# mux1.net
KiCad netlist of a schematic drawn in EAGLE
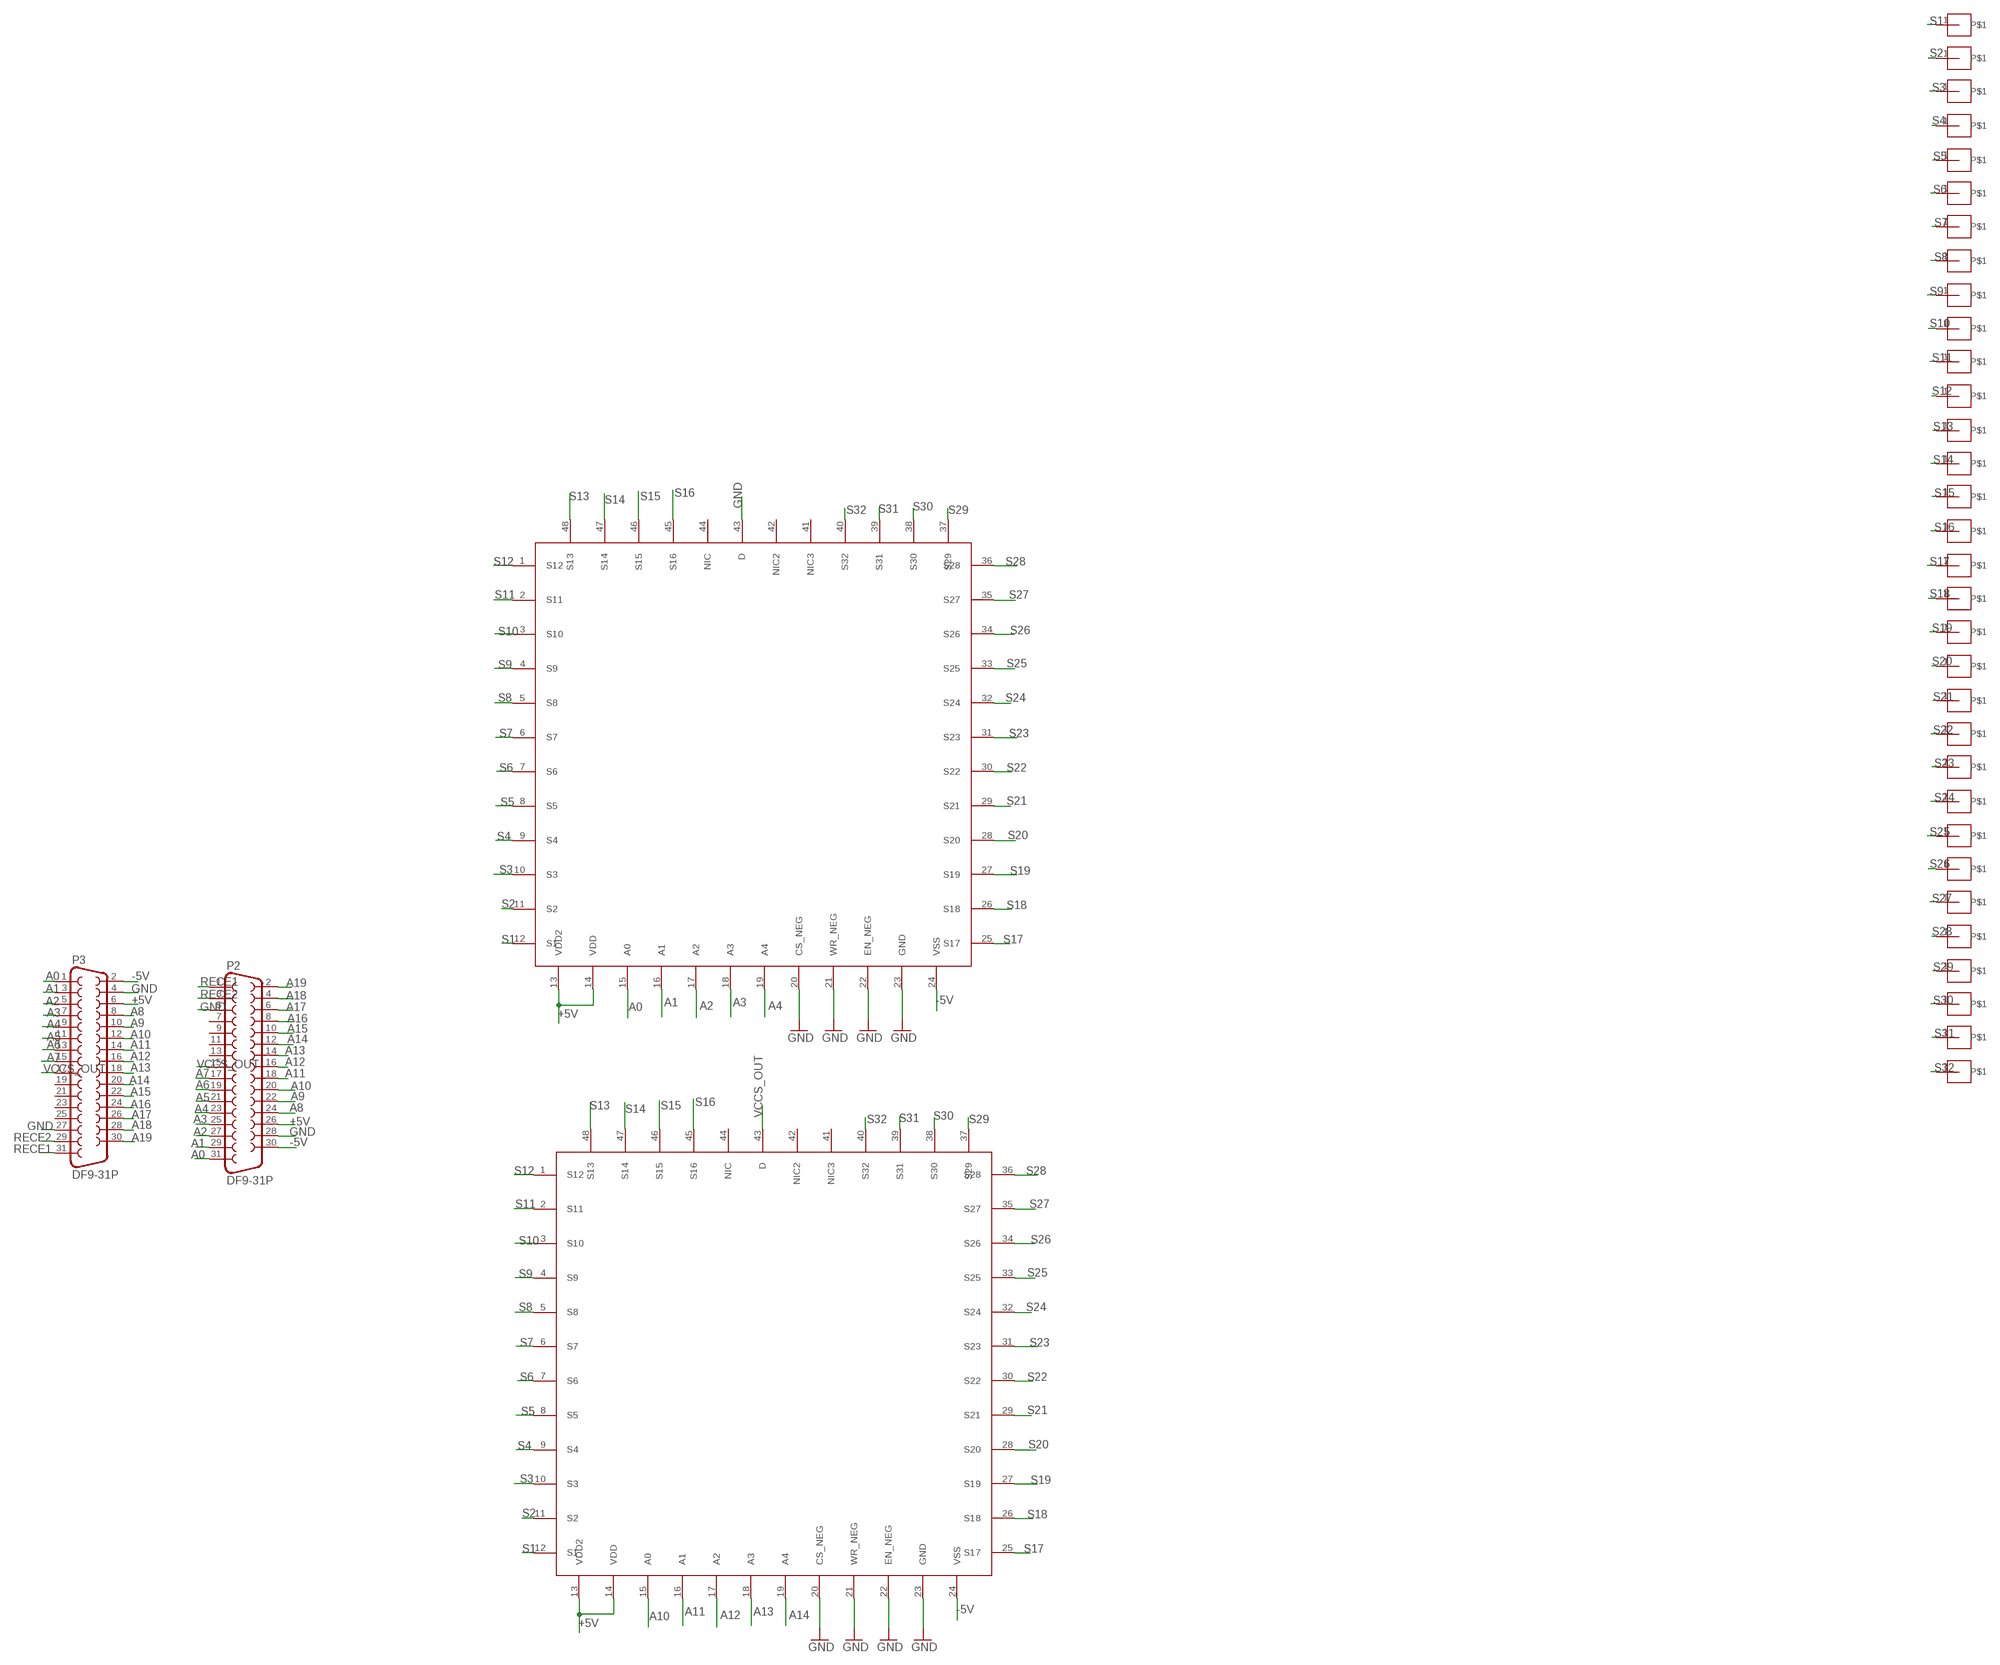
[diagram p0: schematic, sheet 1]

(export (version "E")
  (design (tool "Eeschema 10.0.6"))
  (components
    (comp (ref "P2")
      (value "DF9-31P")
      (footprint "eagle-import:DF9-31P")
      (libsource (lib "eagle-import") (part "DF9-31P"))
    )
    (comp (ref "P3")
      (value "DF9-31P")
      (footprint "eagle-import:DF9-31P")
      (libsource (lib "eagle-import") (part "DF9-31P"))
    )
    (comp (ref "U$3")
      (value "ADG732")
      (footprint "eagle-import:TQFP48")
      (libsource (lib "eagle-import") (part "ADG732"))
    )
    (comp (ref "U$21")
      (value "ADG732")
      (footprint "eagle-import:TQFP48")
      (libsource (lib "eagle-import") (part "ADG732"))
    )
    (comp (ref "U$25")
      (value "M01")
      (footprint "eagle-import:M01")
      (libsource (lib "eagle-import") (part "M01"))
    )
    (comp (ref "U$26")
      (value "M01")
      (footprint "eagle-import:M01")
      (libsource (lib "eagle-import") (part "M01"))
    )
    (comp (ref "U$27")
      (value "M01")
      (footprint "eagle-import:M01")
      (libsource (lib "eagle-import") (part "M01"))
    )
    (comp (ref "U$28")
      (value "M01")
      (footprint "eagle-import:M01")
      (libsource (lib "eagle-import") (part "M01"))
    )
    (comp (ref "U$29")
      (value "M01")
      (footprint "eagle-import:M01")
      (libsource (lib "eagle-import") (part "M01"))
    )
    (comp (ref "U$30")
      (value "M01")
      (footprint "eagle-import:M01")
      (libsource (lib "eagle-import") (part "M01"))
    )
    (comp (ref "U$31")
      (value "M01")
      (footprint "eagle-import:M01")
      (libsource (lib "eagle-import") (part "M01"))
    )
    (comp (ref "U$32")
      (value "M01")
      (footprint "eagle-import:M01")
      (libsource (lib "eagle-import") (part "M01"))
    )
    (comp (ref "U$33")
      (value "M01")
      (footprint "eagle-import:M01")
      (libsource (lib "eagle-import") (part "M01"))
    )
    (comp (ref "U$34")
      (value "M01")
      (footprint "eagle-import:M01")
      (libsource (lib "eagle-import") (part "M01"))
    )
    (comp (ref "U$35")
      (value "M01")
      (footprint "eagle-import:M01")
      (libsource (lib "eagle-import") (part "M01"))
    )
    (comp (ref "U$36")
      (value "M01")
      (footprint "eagle-import:M01")
      (libsource (lib "eagle-import") (part "M01"))
    )
    (comp (ref "U$37")
      (value "M01")
      (footprint "eagle-import:M01")
      (libsource (lib "eagle-import") (part "M01"))
    )
    (comp (ref "U$38")
      (value "M01")
      (footprint "eagle-import:M01")
      (libsource (lib "eagle-import") (part "M01"))
    )
    (comp (ref "U$39")
      (value "M01")
      (footprint "eagle-import:M01")
      (libsource (lib "eagle-import") (part "M01"))
    )
    (comp (ref "U$40")
      (value "M01")
      (footprint "eagle-import:M01")
      (libsource (lib "eagle-import") (part "M01"))
    )
    (comp (ref "U$41")
      (value "M01")
      (footprint "eagle-import:M01")
      (libsource (lib "eagle-import") (part "M01"))
    )
    (comp (ref "U$42")
      (value "M01")
      (footprint "eagle-import:M01")
      (libsource (lib "eagle-import") (part "M01"))
    )
    (comp (ref "U$43")
      (value "M01")
      (footprint "eagle-import:M01")
      (libsource (lib "eagle-import") (part "M01"))
    )
    (comp (ref "U$44")
      (value "M01")
      (footprint "eagle-import:M01")
      (libsource (lib "eagle-import") (part "M01"))
    )
    (comp (ref "U$45")
      (value "M01")
      (footprint "eagle-import:M01")
      (libsource (lib "eagle-import") (part "M01"))
    )
    (comp (ref "U$46")
      (value "M01")
      (footprint "eagle-import:M01")
      (libsource (lib "eagle-import") (part "M01"))
    )
    (comp (ref "U$47")
      (value "M01")
      (footprint "eagle-import:M01")
      (libsource (lib "eagle-import") (part "M01"))
    )
    (comp (ref "U$48")
      (value "M01")
      (footprint "eagle-import:M01")
      (libsource (lib "eagle-import") (part "M01"))
    )
    (comp (ref "U$49")
      (value "M01")
      (footprint "eagle-import:M01")
      (libsource (lib "eagle-import") (part "M01"))
    )
    (comp (ref "U$50")
      (value "M01")
      (footprint "eagle-import:M01")
      (libsource (lib "eagle-import") (part "M01"))
    )
    (comp (ref "U$51")
      (value "M01")
      (footprint "eagle-import:M01")
      (libsource (lib "eagle-import") (part "M01"))
    )
    (comp (ref "U$52")
      (value "M01")
      (footprint "eagle-import:M01")
      (libsource (lib "eagle-import") (part "M01"))
    )
    (comp (ref "U$53")
      (value "M01")
      (footprint "eagle-import:M01")
      (libsource (lib "eagle-import") (part "M01"))
    )
    (comp (ref "U$54")
      (value "M01")
      (footprint "eagle-import:M01")
      (libsource (lib "eagle-import") (part "M01"))
    )
    (comp (ref "U$55")
      (value "M01")
      (footprint "eagle-import:M01")
      (libsource (lib "eagle-import") (part "M01"))
    )
    (comp (ref "U$56")
      (value "M01")
      (footprint "eagle-import:M01")
      (libsource (lib "eagle-import") (part "M01"))
    )
  )
  (nets
    (net (code "1") (name "/+5V") (class "Default")
      (node (ref "P2") (pin "26") (pinfunction "26_26") (pintype "passive"))
      (node (ref "P3") (pin "6") (pinfunction "6_6") (pintype "passive"))
      (node (ref "U$21") (pin "13") (pinfunction "VDD2_13") (pintype "bidirectional"))
      (node (ref "U$21") (pin "14") (pinfunction "VDD_14") (pintype "bidirectional"))
      (node (ref "U$3") (pin "13") (pinfunction "VDD2_13") (pintype "bidirectional"))
      (node (ref "U$3") (pin "14") (pinfunction "VDD_14") (pintype "bidirectional"))
    )
    (net (code "2") (name "/-5V") (class "Default")
      (node (ref "P2") (pin "30") (pinfunction "30_30") (pintype "passive"))
      (node (ref "P3") (pin "2") (pinfunction "2_2") (pintype "passive"))
      (node (ref "U$21") (pin "24") (pinfunction "VSS_24") (pintype "bidirectional"))
      (node (ref "U$3") (pin "24") (pinfunction "VSS_24") (pintype "bidirectional"))
    )
    (net (code "3") (name "/A0") (class "Default")
      (node (ref "P2") (pin "31") (pinfunction "31_31") (pintype "passive"))
      (node (ref "P3") (pin "1") (pinfunction "1_1") (pintype "passive"))
      (node (ref "U$3") (pin "15") (pinfunction "A0_15") (pintype "bidirectional"))
    )
    (net (code "4") (name "/A1") (class "Default")
      (node (ref "P2") (pin "29") (pinfunction "29_29") (pintype "passive"))
      (node (ref "P3") (pin "3") (pinfunction "3_3") (pintype "passive"))
      (node (ref "U$3") (pin "16") (pinfunction "A1_16") (pintype "bidirectional"))
    )
    (net (code "5") (name "/A2") (class "Default")
      (node (ref "P2") (pin "27") (pinfunction "27_27") (pintype "passive"))
      (node (ref "P3") (pin "5") (pinfunction "5_5") (pintype "passive"))
      (node (ref "U$3") (pin "17") (pinfunction "A2_17") (pintype "bidirectional"))
    )
    (net (code "6") (name "/A3") (class "Default")
      (node (ref "P2") (pin "25") (pinfunction "25_25") (pintype "passive"))
      (node (ref "P3") (pin "7") (pinfunction "7_7") (pintype "passive"))
      (node (ref "U$3") (pin "18") (pinfunction "A3_18") (pintype "bidirectional"))
    )
    (net (code "7") (name "/A4") (class "Default")
      (node (ref "P2") (pin "23") (pinfunction "23_23") (pintype "passive"))
      (node (ref "P3") (pin "9") (pinfunction "9_9") (pintype "passive"))
      (node (ref "U$3") (pin "19") (pinfunction "A4_19") (pintype "bidirectional"))
    )
    (net (code "8") (name "/A5") (class "Default")
      (node (ref "P2") (pin "21") (pinfunction "21_21") (pintype "passive"))
      (node (ref "P3") (pin "11") (pinfunction "11_11") (pintype "passive"))
    )
    (net (code "9") (name "/A6") (class "Default")
      (node (ref "P2") (pin "19") (pinfunction "19_19") (pintype "passive"))
      (node (ref "P3") (pin "13") (pinfunction "13_13") (pintype "passive"))
    )
    (net (code "10") (name "/A7") (class "Default")
      (node (ref "P2") (pin "17") (pinfunction "17_17") (pintype "passive"))
      (node (ref "P3") (pin "15") (pinfunction "15_15") (pintype "passive"))
    )
    (net (code "11") (name "/A8") (class "Default")
      (node (ref "P2") (pin "24") (pinfunction "24_24") (pintype "passive"))
      (node (ref "P3") (pin "8") (pinfunction "8_8") (pintype "passive"))
    )
    (net (code "12") (name "/A9") (class "Default")
      (node (ref "P2") (pin "22") (pinfunction "22_22") (pintype "passive"))
      (node (ref "P3") (pin "10") (pinfunction "10_10") (pintype "passive"))
    )
    (net (code "13") (name "/A10") (class "Default")
      (node (ref "P2") (pin "20") (pinfunction "20_20") (pintype "passive"))
      (node (ref "P3") (pin "12") (pinfunction "12_12") (pintype "passive"))
      (node (ref "U$21") (pin "15") (pinfunction "A0_15") (pintype "bidirectional"))
    )
    (net (code "14") (name "/A11") (class "Default")
      (node (ref "P2") (pin "18") (pinfunction "18_18") (pintype "passive"))
      (node (ref "P3") (pin "14") (pinfunction "14_14") (pintype "passive"))
      (node (ref "U$21") (pin "16") (pinfunction "A1_16") (pintype "bidirectional"))
    )
    (net (code "15") (name "/A12") (class "Default")
      (node (ref "P2") (pin "16") (pinfunction "16_16") (pintype "passive"))
      (node (ref "P3") (pin "16") (pinfunction "16_16") (pintype "passive"))
      (node (ref "U$21") (pin "17") (pinfunction "A2_17") (pintype "bidirectional"))
    )
    (net (code "16") (name "/A13") (class "Default")
      (node (ref "P2") (pin "14") (pinfunction "14_14") (pintype "passive"))
      (node (ref "P3") (pin "18") (pinfunction "18_18") (pintype "passive"))
      (node (ref "U$21") (pin "18") (pinfunction "A3_18") (pintype "bidirectional"))
    )
    (net (code "17") (name "/A14") (class "Default")
      (node (ref "P2") (pin "12") (pinfunction "12_12") (pintype "passive"))
      (node (ref "P3") (pin "20") (pinfunction "20_20") (pintype "passive"))
      (node (ref "U$21") (pin "19") (pinfunction "A4_19") (pintype "bidirectional"))
    )
    (net (code "18") (name "/A15") (class "Default")
      (node (ref "P2") (pin "10") (pinfunction "10_10") (pintype "passive"))
      (node (ref "P3") (pin "22") (pinfunction "22_22") (pintype "passive"))
    )
    (net (code "19") (name "/A16") (class "Default")
      (node (ref "P2") (pin "8") (pinfunction "8_8") (pintype "passive"))
      (node (ref "P3") (pin "24") (pinfunction "24_24") (pintype "passive"))
    )
    (net (code "20") (name "/A17") (class "Default")
      (node (ref "P2") (pin "6") (pinfunction "6_6") (pintype "passive"))
      (node (ref "P3") (pin "26") (pinfunction "26_26") (pintype "passive"))
    )
    (net (code "21") (name "/A18") (class "Default")
      (node (ref "P2") (pin "4") (pinfunction "4_4") (pintype "passive"))
      (node (ref "P3") (pin "28") (pinfunction "28_28") (pintype "passive"))
    )
    (net (code "22") (name "/A19") (class "Default")
      (node (ref "P2") (pin "2") (pinfunction "2_2") (pintype "passive"))
      (node (ref "P3") (pin "30") (pinfunction "30_30") (pintype "passive"))
    )
    (net (code "23") (name "/RECE1") (class "Default")
      (node (ref "P2") (pin "1") (pinfunction "1_1") (pintype "passive"))
      (node (ref "P3") (pin "31") (pinfunction "31_31") (pintype "passive"))
    )
    (net (code "24") (name "/RECE2") (class "Default")
      (node (ref "P2") (pin "3") (pinfunction "3_3") (pintype "passive"))
      (node (ref "P3") (pin "29") (pinfunction "29_29") (pintype "passive"))
    )
    (net (code "25") (name "/S1") (class "Default")
      (node (ref "U$21") (pin "12") (pinfunction "S1_12") (pintype "bidirectional"))
      (node (ref "U$25") (pin "1") (pinfunction "P$1_1") (pintype "bidirectional"))
      (node (ref "U$3") (pin "12") (pinfunction "S1_12") (pintype "bidirectional"))
    )
    (net (code "26") (name "/S2") (class "Default")
      (node (ref "U$21") (pin "11") (pinfunction "S2_11") (pintype "bidirectional"))
      (node (ref "U$26") (pin "1") (pinfunction "P$1_1") (pintype "bidirectional"))
      (node (ref "U$3") (pin "11") (pinfunction "S2_11") (pintype "bidirectional"))
    )
    (net (code "27") (name "/S3") (class "Default")
      (node (ref "U$21") (pin "10") (pinfunction "S3_10") (pintype "bidirectional"))
      (node (ref "U$27") (pin "1") (pinfunction "P$1_1") (pintype "bidirectional"))
      (node (ref "U$3") (pin "10") (pinfunction "S3_10") (pintype "bidirectional"))
    )
    (net (code "28") (name "/S4") (class "Default")
      (node (ref "U$21") (pin "9") (pinfunction "S4_9") (pintype "bidirectional"))
      (node (ref "U$28") (pin "1") (pinfunction "P$1_1") (pintype "bidirectional"))
      (node (ref "U$3") (pin "9") (pinfunction "S4_9") (pintype "bidirectional"))
    )
    (net (code "29") (name "/S5") (class "Default")
      (node (ref "U$21") (pin "8") (pinfunction "S5_8") (pintype "bidirectional"))
      (node (ref "U$29") (pin "1") (pinfunction "P$1_1") (pintype "bidirectional"))
      (node (ref "U$3") (pin "8") (pinfunction "S5_8") (pintype "bidirectional"))
    )
    (net (code "30") (name "/S6") (class "Default")
      (node (ref "U$21") (pin "7") (pinfunction "S6_7") (pintype "bidirectional"))
      (node (ref "U$3") (pin "7") (pinfunction "S6_7") (pintype "bidirectional"))
      (node (ref "U$30") (pin "1") (pinfunction "P$1_1") (pintype "bidirectional"))
    )
    (net (code "31") (name "/S7") (class "Default")
      (node (ref "U$21") (pin "6") (pinfunction "S7_6") (pintype "bidirectional"))
      (node (ref "U$3") (pin "6") (pinfunction "S7_6") (pintype "bidirectional"))
      (node (ref "U$31") (pin "1") (pinfunction "P$1_1") (pintype "bidirectional"))
    )
    (net (code "32") (name "/S8") (class "Default")
      (node (ref "U$21") (pin "5") (pinfunction "S8_5") (pintype "bidirectional"))
      (node (ref "U$3") (pin "5") (pinfunction "S8_5") (pintype "bidirectional"))
      (node (ref "U$32") (pin "1") (pinfunction "P$1_1") (pintype "bidirectional"))
    )
    (net (code "33") (name "/S9") (class "Default")
      (node (ref "U$21") (pin "4") (pinfunction "S9_4") (pintype "bidirectional"))
      (node (ref "U$3") (pin "4") (pinfunction "S9_4") (pintype "bidirectional"))
      (node (ref "U$33") (pin "1") (pinfunction "P$1_1") (pintype "bidirectional"))
    )
    (net (code "34") (name "/S10") (class "Default")
      (node (ref "U$21") (pin "3") (pinfunction "S10_3") (pintype "bidirectional"))
      (node (ref "U$3") (pin "3") (pinfunction "S10_3") (pintype "bidirectional"))
      (node (ref "U$34") (pin "1") (pinfunction "P$1_1") (pintype "bidirectional"))
    )
    (net (code "35") (name "/S11") (class "Default")
      (node (ref "U$21") (pin "2") (pinfunction "S11_2") (pintype "bidirectional"))
      (node (ref "U$3") (pin "2") (pinfunction "S11_2") (pintype "bidirectional"))
      (node (ref "U$35") (pin "1") (pinfunction "P$1_1") (pintype "bidirectional"))
    )
    (net (code "36") (name "/S12") (class "Default")
      (node (ref "U$21") (pin "1") (pinfunction "S12_1") (pintype "bidirectional"))
      (node (ref "U$3") (pin "1") (pinfunction "S12_1") (pintype "bidirectional"))
      (node (ref "U$36") (pin "1") (pinfunction "P$1_1") (pintype "bidirectional"))
    )
    (net (code "37") (name "/S13") (class "Default")
      (node (ref "U$21") (pin "48") (pinfunction "S13_48") (pintype "bidirectional"))
      (node (ref "U$3") (pin "48") (pinfunction "S13_48") (pintype "bidirectional"))
      (node (ref "U$37") (pin "1") (pinfunction "P$1_1") (pintype "bidirectional"))
    )
    (net (code "38") (name "/S14") (class "Default")
      (node (ref "U$21") (pin "47") (pinfunction "S14_47") (pintype "bidirectional"))
      (node (ref "U$3") (pin "47") (pinfunction "S14_47") (pintype "bidirectional"))
      (node (ref "U$38") (pin "1") (pinfunction "P$1_1") (pintype "bidirectional"))
    )
    (net (code "39") (name "/S15") (class "Default")
      (node (ref "U$21") (pin "46") (pinfunction "S15_46") (pintype "bidirectional"))
      (node (ref "U$3") (pin "46") (pinfunction "S15_46") (pintype "bidirectional"))
      (node (ref "U$39") (pin "1") (pinfunction "P$1_1") (pintype "bidirectional"))
    )
    (net (code "40") (name "/S16") (class "Default")
      (node (ref "U$21") (pin "45") (pinfunction "S16_45") (pintype "bidirectional"))
      (node (ref "U$3") (pin "45") (pinfunction "S16_45") (pintype "bidirectional"))
      (node (ref "U$40") (pin "1") (pinfunction "P$1_1") (pintype "bidirectional"))
    )
    (net (code "41") (name "/S17") (class "Default")
      (node (ref "U$21") (pin "25") (pinfunction "S17_25") (pintype "bidirectional"))
      (node (ref "U$3") (pin "25") (pinfunction "S17_25") (pintype "bidirectional"))
      (node (ref "U$41") (pin "1") (pinfunction "P$1_1") (pintype "bidirectional"))
    )
    (net (code "42") (name "/S18") (class "Default")
      (node (ref "U$21") (pin "26") (pinfunction "S18_26") (pintype "bidirectional"))
      (node (ref "U$3") (pin "26") (pinfunction "S18_26") (pintype "bidirectional"))
      (node (ref "U$42") (pin "1") (pinfunction "P$1_1") (pintype "bidirectional"))
    )
    (net (code "43") (name "/S19") (class "Default")
      (node (ref "U$21") (pin "27") (pinfunction "S19_27") (pintype "bidirectional"))
      (node (ref "U$3") (pin "27") (pinfunction "S19_27") (pintype "bidirectional"))
      (node (ref "U$43") (pin "1") (pinfunction "P$1_1") (pintype "bidirectional"))
    )
    (net (code "44") (name "/S20") (class "Default")
      (node (ref "U$21") (pin "28") (pinfunction "S20_28") (pintype "bidirectional"))
      (node (ref "U$3") (pin "28") (pinfunction "S20_28") (pintype "bidirectional"))
      (node (ref "U$44") (pin "1") (pinfunction "P$1_1") (pintype "bidirectional"))
    )
    (net (code "45") (name "/S21") (class "Default")
      (node (ref "U$21") (pin "29") (pinfunction "S21_29") (pintype "bidirectional"))
      (node (ref "U$3") (pin "29") (pinfunction "S21_29") (pintype "bidirectional"))
      (node (ref "U$45") (pin "1") (pinfunction "P$1_1") (pintype "bidirectional"))
    )
    (net (code "46") (name "/S22") (class "Default")
      (node (ref "U$21") (pin "30") (pinfunction "S22_30") (pintype "bidirectional"))
      (node (ref "U$3") (pin "30") (pinfunction "S22_30") (pintype "bidirectional"))
      (node (ref "U$46") (pin "1") (pinfunction "P$1_1") (pintype "bidirectional"))
    )
    (net (code "47") (name "/S23") (class "Default")
      (node (ref "U$21") (pin "31") (pinfunction "S23_31") (pintype "bidirectional"))
      (node (ref "U$3") (pin "31") (pinfunction "S23_31") (pintype "bidirectional"))
      (node (ref "U$47") (pin "1") (pinfunction "P$1_1") (pintype "bidirectional"))
    )
    (net (code "48") (name "/S24") (class "Default")
      (node (ref "U$21") (pin "32") (pinfunction "S24_32") (pintype "bidirectional"))
      (node (ref "U$3") (pin "32") (pinfunction "S24_32") (pintype "bidirectional"))
      (node (ref "U$48") (pin "1") (pinfunction "P$1_1") (pintype "bidirectional"))
    )
    (net (code "49") (name "/S25") (class "Default")
      (node (ref "U$21") (pin "33") (pinfunction "S25_33") (pintype "bidirectional"))
      (node (ref "U$3") (pin "33") (pinfunction "S25_33") (pintype "bidirectional"))
      (node (ref "U$49") (pin "1") (pinfunction "P$1_1") (pintype "bidirectional"))
    )
    (net (code "50") (name "/S26") (class "Default")
      (node (ref "U$21") (pin "34") (pinfunction "S26_34") (pintype "bidirectional"))
      (node (ref "U$3") (pin "34") (pinfunction "S26_34") (pintype "bidirectional"))
      (node (ref "U$50") (pin "1") (pinfunction "P$1_1") (pintype "bidirectional"))
    )
    (net (code "51") (name "/S27") (class "Default")
      (node (ref "U$21") (pin "35") (pinfunction "S27_35") (pintype "bidirectional"))
      (node (ref "U$3") (pin "35") (pinfunction "S27_35") (pintype "bidirectional"))
      (node (ref "U$51") (pin "1") (pinfunction "P$1_1") (pintype "bidirectional"))
    )
    (net (code "52") (name "/S28") (class "Default")
      (node (ref "U$21") (pin "36") (pinfunction "S28_36") (pintype "bidirectional"))
      (node (ref "U$3") (pin "36") (pinfunction "S28_36") (pintype "bidirectional"))
      (node (ref "U$52") (pin "1") (pinfunction "P$1_1") (pintype "bidirectional"))
    )
    (net (code "53") (name "/S29") (class "Default")
      (node (ref "U$21") (pin "37") (pinfunction "S29_37") (pintype "bidirectional"))
      (node (ref "U$3") (pin "37") (pinfunction "S29_37") (pintype "bidirectional"))
      (node (ref "U$53") (pin "1") (pinfunction "P$1_1") (pintype "bidirectional"))
    )
    (net (code "54") (name "/S30") (class "Default")
      (node (ref "U$21") (pin "38") (pinfunction "S30_38") (pintype "bidirectional"))
      (node (ref "U$3") (pin "38") (pinfunction "S30_38") (pintype "bidirectional"))
      (node (ref "U$54") (pin "1") (pinfunction "P$1_1") (pintype "bidirectional"))
    )
    (net (code "55") (name "/S31") (class "Default")
      (node (ref "U$21") (pin "39") (pinfunction "S31_39") (pintype "bidirectional"))
      (node (ref "U$3") (pin "39") (pinfunction "S31_39") (pintype "bidirectional"))
      (node (ref "U$55") (pin "1") (pinfunction "P$1_1") (pintype "bidirectional"))
    )
    (net (code "56") (name "/S32") (class "Default")
      (node (ref "U$21") (pin "40") (pinfunction "S32_40") (pintype "bidirectional"))
      (node (ref "U$3") (pin "40") (pinfunction "S32_40") (pintype "bidirectional"))
      (node (ref "U$56") (pin "1") (pinfunction "P$1_1") (pintype "bidirectional"))
    )
    (net (code "57") (name "/VCCS_OUT") (class "Default")
      (node (ref "P2") (pin "15") (pinfunction "15_15") (pintype "passive"))
      (node (ref "P3") (pin "17") (pinfunction "17_17") (pintype "passive"))
      (node (ref "U$21") (pin "43") (pinfunction "D_43") (pintype "bidirectional"))
    )
    (net (code "58") (name "GND") (class "Default")
      (node (ref "P2") (pin "28") (pinfunction "28_28") (pintype "passive"))
      (node (ref "P2") (pin "5") (pinfunction "5_5") (pintype "passive"))
      (node (ref "P3") (pin "27") (pinfunction "27_27") (pintype "passive"))
      (node (ref "P3") (pin "4") (pinfunction "4_4") (pintype "passive"))
      (node (ref "U$21") (pin "20") (pinfunction "CS_NEG_20") (pintype "bidirectional"))
      (node (ref "U$21") (pin "21") (pinfunction "WR_NEG_21") (pintype "bidirectional"))
      (node (ref "U$21") (pin "22") (pinfunction "EN_NEG_22") (pintype "bidirectional"))
      (node (ref "U$21") (pin "23") (pinfunction "GND_23") (pintype "bidirectional"))
      (node (ref "U$3") (pin "20") (pinfunction "CS_NEG_20") (pintype "bidirectional"))
      (node (ref "U$3") (pin "21") (pinfunction "WR_NEG_21") (pintype "bidirectional"))
      (node (ref "U$3") (pin "22") (pinfunction "EN_NEG_22") (pintype "bidirectional"))
      (node (ref "U$3") (pin "23") (pinfunction "GND_23") (pintype "bidirectional"))
      (node (ref "U$3") (pin "43") (pinfunction "D_43") (pintype "bidirectional"))
    )
    (net (code "59") (name "unconnected-(P2-Pad7)") (class "Default")
      (node (ref "P2") (pin "7") (pinfunction "7_7") (pintype "passive"))
    )
    (net (code "60") (name "unconnected-(P2-Pad9)") (class "Default")
      (node (ref "P2") (pin "9") (pinfunction "9_9") (pintype "passive"))
    )
    (net (code "61") (name "unconnected-(P2-Pad11)") (class "Default")
      (node (ref "P2") (pin "11") (pinfunction "11_11") (pintype "passive"))
    )
    (net (code "62") (name "unconnected-(P2-Pad13)") (class "Default")
      (node (ref "P2") (pin "13") (pinfunction "13_13") (pintype "passive"))
    )
    (net (code "63") (name "unconnected-(P3-Pad19)") (class "Default")
      (node (ref "P3") (pin "19") (pinfunction "19_19") (pintype "passive"))
    )
    (net (code "64") (name "unconnected-(P3-Pad21)") (class "Default")
      (node (ref "P3") (pin "21") (pinfunction "21_21") (pintype "passive"))
    )
    (net (code "65") (name "unconnected-(P3-Pad23)") (class "Default")
      (node (ref "P3") (pin "23") (pinfunction "23_23") (pintype "passive"))
    )
    (net (code "66") (name "unconnected-(P3-Pad25)") (class "Default")
      (node (ref "P3") (pin "25") (pinfunction "25_25") (pintype "passive"))
    )
    (net (code "67") (name "unconnected-(U$3-NIC-Pad44)") (class "Default")
      (node (ref "U$3") (pin "44") (pinfunction "NIC_44") (pintype "bidirectional"))
    )
    (net (code "68") (name "unconnected-(U$3-NIC2-Pad42)") (class "Default")
      (node (ref "U$3") (pin "42") (pinfunction "NIC2_42") (pintype "bidirectional"))
    )
    (net (code "69") (name "unconnected-(U$3-NIC3-Pad41)") (class "Default")
      (node (ref "U$3") (pin "41") (pinfunction "NIC3_41") (pintype "bidirectional"))
    )
    (net (code "70") (name "unconnected-(U$21-NIC-Pad44)") (class "Default")
      (node (ref "U$21") (pin "44") (pinfunction "NIC_44") (pintype "bidirectional"))
    )
    (net (code "71") (name "unconnected-(U$21-NIC2-Pad42)") (class "Default")
      (node (ref "U$21") (pin "42") (pinfunction "NIC2_42") (pintype "bidirectional"))
    )
    (net (code "72") (name "unconnected-(U$21-NIC3-Pad41)") (class "Default")
      (node (ref "U$21") (pin "41") (pinfunction "NIC3_41") (pintype "bidirectional"))
    )
  )
)
